# Stepping_Motor_DriverC.net
KiCad netlist of a schematic drawn in Altium Designer
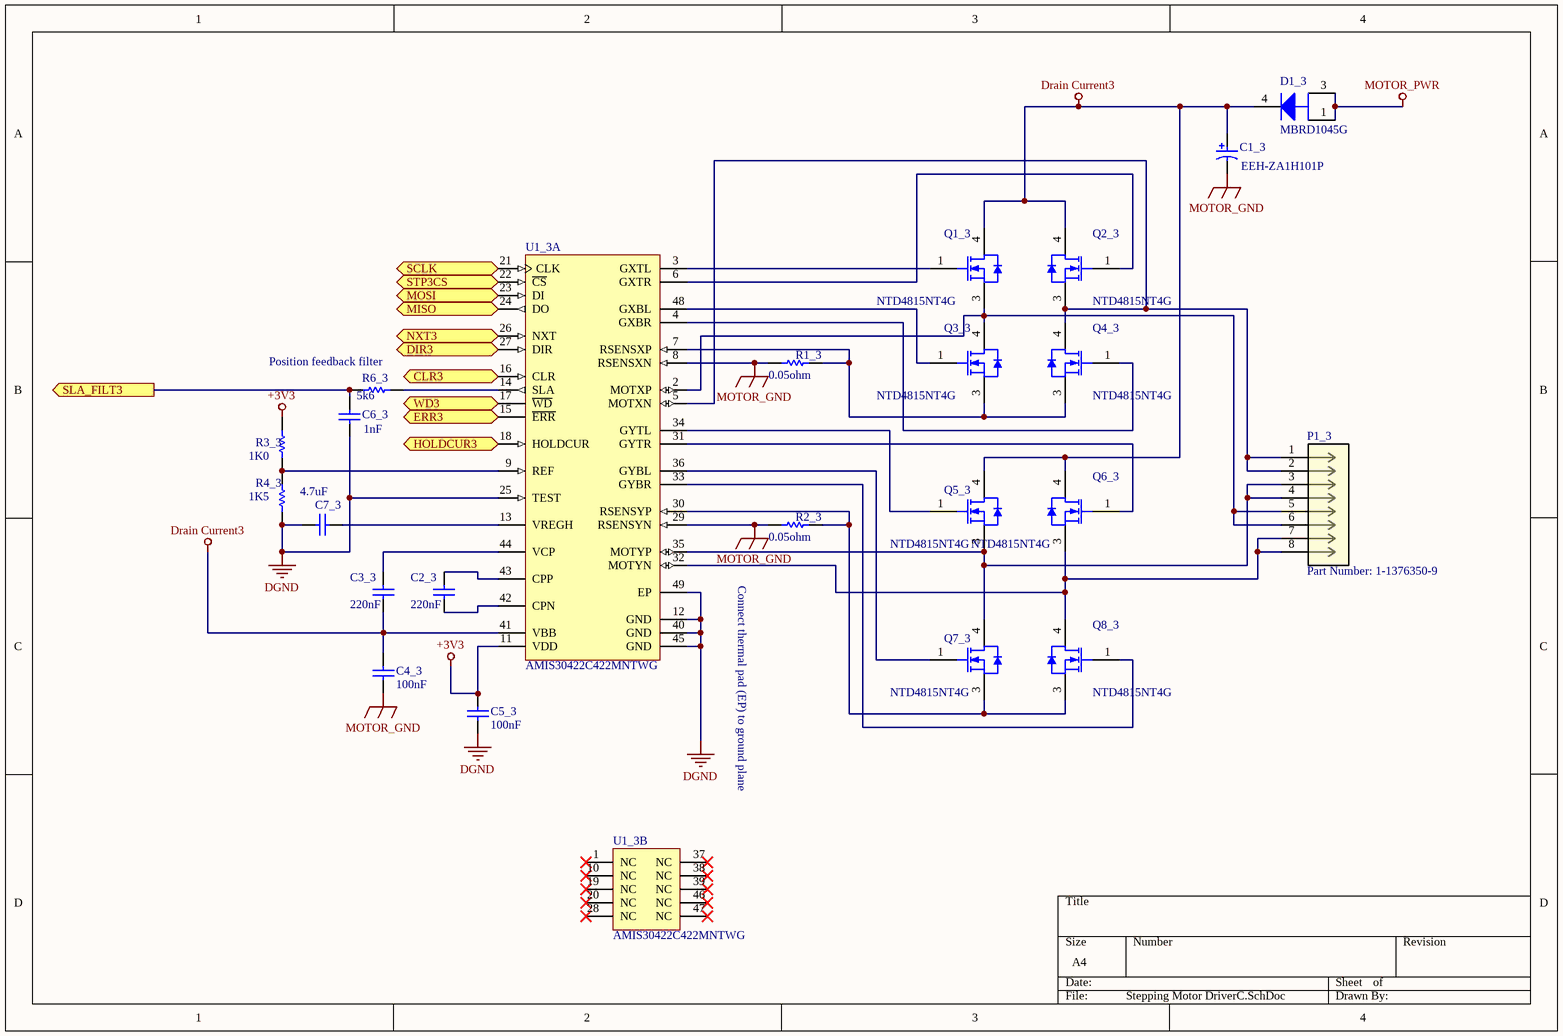
[diagram p0: Stepping Motor DriverC.SchDoc]

(export (version "E")
  (design (tool "Eeschema 10.0.6"))
  (components
    (comp (ref "C1_3")
      (value "EEH-ZA1H101P")
      (footprint "PNSC-ZA-G_L")
      (fields (field (name "TOLERANCE") "20%") (field (name "MANUFACTURER") "Panasonic"))
      (libsource (lib "Altium Content Vault") (part "CAP-P-2"))
    )
    (comp (ref "C2_3")
      (value "220nF")
      (footprint "CAPC0805(2012)75_L")
      (description "CAP 220nF 50V -20% to +80% 0805 (2012 Metric) Thickness 0.75mm SMD")
      (fields (field (name "TOLERANCE") "-20% to +80%") (field (name "Comment") "CAP 220nF 50V 0805(2012)"))
      (libsource (lib "Altium Content Vault") (part "CMP-1036-04556-1"))
    )
    (comp (ref "C3_3")
      (value "220nF")
      (footprint "CAPC0805(2012)75_L")
      (description "CAP 220nF 50V -20% to +80% 0805 (2012 Metric) Thickness 0.75mm SMD")
      (fields (field (name "TOLERANCE") "-20% to +80%") (field (name "Comment") "CAP 220nF 50V 0805(2012)"))
      (libsource (lib "Altium Content Vault") (part "CMP-1036-04556-1"))
    )
    (comp (ref "C4_3")
      (value "100nF")
      (footprint "CAPC1812(4532)110_N")
      (description "CAP 100nF 50V ±20% 1812 (4532 Metric) Thickness 1.1mm SMD")
      (fields (field (name "TOLERANCE") "Â±20%") (field (name "Comment") "CAP 100nF 50V 1812(4532)"))
      (libsource (lib "Altium Content Vault") (part "CMP-1040-01292-1"))
    )
    (comp (ref "C5_3")
      (value "100nF")
      (footprint "CAPC1812(4532)110_N")
      (description "CAP 100nF 50V ±20% 1812 (4532 Metric) Thickness 1.1mm SMD")
      (fields (field (name "TOLERANCE") "Â±20%") (field (name "Comment") "CAP 100nF 50V 1812(4532)"))
      (libsource (lib "Altium Content Vault") (part "CMP-1040-01292-1"))
    )
    (comp (ref "C6_3")
      (value "1nF")
      (footprint "CAPC1206(3216)170_N")
      (description "CAP 1nF 50V ±2% 1206 (3216 Metric) Thickness 1.7mm SMD")
      (fields (field (name "TOLERANCE") "Â±2%") (field (name "Comment") "CAP 1nF 50V 1206(3216)"))
      (libsource (lib "Altium Content Vault") (part "CMP-1037-02447-1"))
    )
    (comp (ref "C7_3")
      (value "4.7uF")
      (footprint "CAPC2220(5750)230_L")
      (description "CAP 4.7uF 50V ±10% 2220 (5750 Metric) Thickness 2.2mm SMD")
      (fields (field (name "TOLERANCE") "Â±10%") (field (name "Comment") "CAP 4.7uF 50V 2220(5750)"))
      (libsource (lib "Altium Content Vault") (part "CMP-1042-00755-1"))
    )
    (comp (ref "D1_3")
      (value "MBRD1045G")
      (footprint "ONSC-DPAK-3-369C-01_V")
      (description "SWITCHMODE(TM) Schottky Power Rectifier, 3-Pin DPAK, Pb-Free, Tube")
      (fields (field (name "MANUFACTURER") "On Semiconductor"))
      (libsource (lib "Altium Content Vault") (part "ONSC-D-A1A3K4-3_A"))
    )
    (comp (ref "P1_3")
      (value "Part Number: 1-1376350-9")
      (footprint "conn8_1-1376350-")
      (description "025 8POS CAP ASSY H TIN")
      (fields
        (field (name "MANUFACTURER_PART_NUMBER") "1-1376350-9")
        (field (name "COPYRIGHT") "Copyright (C) 2018 Accelerated Designs. All rights reserved")
      )
      (libsource (lib "2020-04-08_04-40-03") (part "1-1376350-9"))
    )
    (comp (ref "Q1_3")
      (value "NTD4815NT4G")
      (footprint "ONSC-DPAK-3-369AA-01_V")
      (description "Power MOSFET, 30 V, 35 A, Single N-Channel, 3-Pin DPAK, Pb-Free, Tape and Reel")
      (fields (field (name "MANUFACTURER") "On Semiconductor"))
      (libsource (lib "Altium Content Vault") (part "ONSC-NMOS-G1S3D4-3_B"))
    )
    (comp (ref "Q2_3")
      (value "NTD4815NT4G")
      (footprint "ONSC-DPAK-3-369AA-01_V")
      (description "Power MOSFET, 30 V, 35 A, Single N-Channel, 3-Pin DPAK, Pb-Free, Tape and Reel")
      (fields (field (name "MANUFACTURER") "On Semiconductor"))
      (libsource (lib "Altium Content Vault") (part "CMP-1058-00298-1"))
    )
    (comp (ref "Q3_3")
      (value "NTD4815NT4G")
      (footprint "ONSC-DPAK-3-369AA-01_V")
      (description "Power MOSFET, 30 V, 35 A, Single N-Channel, 3-Pin DPAK, Pb-Free, Tape and Reel")
      (fields (field (name "MANUFACTURER") "On Semiconductor"))
      (libsource (lib "Altium Content Vault") (part "ONSC-NMOS-G1S3D4-3_B"))
    )
    (comp (ref "Q4_3")
      (value "NTD4815NT4G")
      (footprint "ONSC-DPAK-3-369AA-01_V")
      (description "Power MOSFET, 30 V, 35 A, Single N-Channel, 3-Pin DPAK, Pb-Free, Tape and Reel")
      (fields (field (name "MANUFACTURER") "On Semiconductor"))
      (libsource (lib "Altium Content Vault") (part "CMP-1058-00298-1"))
    )
    (comp (ref "Q5_3")
      (value "NTD4815NT4G")
      (footprint "ONSC-DPAK-3-369AA-01_V")
      (description "Power MOSFET, 30 V, 35 A, Single N-Channel, 3-Pin DPAK, Pb-Free, Tape and Reel")
      (fields (field (name "MANUFACTURER") "On Semiconductor"))
      (libsource (lib "Altium Content Vault") (part "ONSC-NMOS-G1S3D4-3_B"))
    )
    (comp (ref "Q6_3")
      (value "NTD4815NT4G")
      (footprint "ONSC-DPAK-3-369AA-01_V")
      (description "Power MOSFET, 30 V, 35 A, Single N-Channel, 3-Pin DPAK, Pb-Free, Tape and Reel")
      (fields (field (name "MANUFACTURER") "On Semiconductor"))
      (libsource (lib "Altium Content Vault") (part "CMP-1058-00298-1"))
    )
    (comp (ref "Q7_3")
      (value "NTD4815NT4G")
      (footprint "ONSC-DPAK-3-369AA-01_V")
      (description "Power MOSFET, 30 V, 35 A, Single N-Channel, 3-Pin DPAK, Pb-Free, Tape and Reel")
      (fields (field (name "MANUFACTURER") "On Semiconductor"))
      (libsource (lib "Altium Content Vault") (part "ONSC-NMOS-G1S3D4-3_B"))
    )
    (comp (ref "Q8_3")
      (value "NTD4815NT4G")
      (footprint "ONSC-DPAK-3-369AA-01_V")
      (description "Power MOSFET, 30 V, 35 A, Single N-Channel, 3-Pin DPAK, Pb-Free, Tape and Reel")
      (fields (field (name "MANUFACTURER") "On Semiconductor"))
      (libsource (lib "Altium Content Vault") (part "CMP-1058-00298-1"))
    )
    (comp (ref "R1_3")
      (value "WSL2512R0500FEA")
      (footprint "RESC6432X89X76LL25T25")
      (description "Chip Resistor, 50 mOhm, +/- 1%, 1 W, -65 to 170 degC, 2512 (6432 Metric), RoHS, Tape and Reel")
      (fields (field (name "MANUFACTURER") "Vishay") (field (name "RESISTANCE") "0.05ohm"))
      (libsource (lib "Altium Content Vault") (part "CMP-2000-07420-1"))
    )
    (comp (ref "R2_3")
      (value "WSL2512R0500FEA")
      (footprint "RESC6432X89X76LL25T25")
      (description "Chip Resistor, 50 mOhm, +/- 1%, 1 W, -65 to 170 degC, 2512 (6432 Metric), RoHS, Tape and Reel")
      (fields (field (name "MANUFACTURER") "Vishay") (field (name "RESISTANCE") "0.05ohm"))
      (libsource (lib "Altium Content Vault") (part "CMP-2000-07420-1"))
    )
    (comp (ref "R3_3")
      (value "1K0")
      (footprint "RESC0805(2012)_M")
      (description "1K 0.125W 1% 0805 (2012 Metric)  SMD")
      (fields (field (name "TOLERANCE") "1 %") (field (name "POWER") "0.125 W"))
      (libsource (lib "Altium Content Vault") (part "CMP-1013-00510-1"))
    )
    (comp (ref "R4_3")
      (value "1K5")
      (footprint "RESC0805(2012)_M")
      (description "1K5 0.125W 1% 0805 (2012 Metric)  SMD")
      (fields (field (name "POWER") "0.125 W") (field (name "TOLERANCE") "1 %"))
      (libsource (lib "Altium Content Vault") (part "CMP-1013-00528-1"))
    )
    (comp (ref "R6_3")
      (value "5k6")
      (footprint "RESC0805(2012)_L")
      (description "5K6 0.125W 1% 0805 (2012 Metric)  SMD")
      (fields (field (name "POWER") "0.125 W") (field (name "TOLERANCE") "1 %"))
      (libsource (lib "Altium Content Vault") (part "CMP-1013-00595-1"))
    )
    (comp (ref "U1_3")
      (value "AMIS30422C422MNTWG")
      (footprint "ONSC-QFN-48-485AJ-01_V")
      (fields (field (name "MANUFACTURER") "ON Semiconductor"))
      (libsource (lib "Altium Content Vault") (part "ONSC-AMIS-30422-QFN-48"))
    )
  )
  (nets
    (net (code "1") (name "+3V3") (class "Default")
      (node (ref "C5_3") (pin "2") (pinfunction "2_2") (pintype "passive"))
      (node (ref "R3_3") (pin "2") (pinfunction "2_2") (pintype "passive"))
      (node (ref "U1_3") (pin "11") (pinfunction "VDD_11") (pintype "power_in"))
    )
    (net (code "2") (name "/CLR3") (class "Default")
      (node (ref "U1_3") (pin "16") (pinfunction "CLR_16") (pintype "input"))
    )
    (net (code "3") (name "/DIR3") (class "Default")
      (node (ref "U1_3") (pin "27") (pinfunction "DIR_27") (pintype "input"))
    )
    (net (code "4") (name "/ERR3") (class "Default")
      (node (ref "U1_3") (pin "15") (pinfunction "~{ERR}_15") (pintype "tri_state"))
    )
    (net (code "5") (name "/HOLDCUR3") (class "Default")
      (node (ref "U1_3") (pin "18") (pinfunction "HOLDCUR_18") (pintype "input"))
    )
    (net (code "6") (name "/MISO") (class "Default")
      (node (ref "U1_3") (pin "24") (pinfunction "DO_24") (pintype "output"))
    )
    (net (code "7") (name "/MOSI") (class "Default")
      (node (ref "U1_3") (pin "23") (pinfunction "DI_23") (pintype "input"))
    )
    (net (code "8") (name "/NXT3") (class "Default")
      (node (ref "U1_3") (pin "26") (pinfunction "NXT_26") (pintype "input"))
    )
    (net (code "9") (name "/SCLK") (class "Default")
      (node (ref "U1_3") (pin "21") (pinfunction "CLK_21") (pintype "input"))
    )
    (net (code "10") (name "/SLA_FILT3") (class "Default")
      (node (ref "C6_3") (pin "2") (pinfunction "2_2") (pintype "passive"))
      (node (ref "R6_3") (pin "1") (pinfunction "1_1") (pintype "passive"))
    )
    (net (code "11") (name "/STP3CS") (class "Default")
      (node (ref "U1_3") (pin "22") (pinfunction "~{CS}_22") (pintype "input"))
    )
    (net (code "12") (name "/WD3") (class "Default")
      (node (ref "U1_3") (pin "17") (pinfunction "~{WD}_17") (pintype "tri_state"))
    )
    (net (code "13") (name "DGND") (class "Default")
      (node (ref "C5_3") (pin "1") (pinfunction "1_1") (pintype "passive"))
      (node (ref "C6_3") (pin "1") (pinfunction "1_1") (pintype "passive"))
      (node (ref "C7_3") (pin "1") (pinfunction "1_1") (pintype "passive"))
      (node (ref "R4_3") (pin "1") (pinfunction "1_1") (pintype "passive"))
      (node (ref "U1_3") (pin "12") (pinfunction "GND_12") (pintype "power_in"))
      (node (ref "U1_3") (pin "25") (pinfunction "TEST_25") (pintype "input"))
      (node (ref "U1_3") (pin "40") (pinfunction "GND_40") (pintype "power_in"))
      (node (ref "U1_3") (pin "45") (pinfunction "GND_45") (pintype "power_in"))
      (node (ref "U1_3") (pin "49") (pinfunction "EP_49") (pintype "passive"))
    )
    (net (code "14") (name "Drain Current3") (class "Default")
      (node (ref "C1_3") (pin "1") (pinfunction "1_1") (pintype "passive"))
      (node (ref "C3_3") (pin "1") (pinfunction "1_1") (pintype "passive"))
      (node (ref "C4_3") (pin "2") (pinfunction "2_2") (pintype "passive"))
      (node (ref "D1_3") (pin "4") (pinfunction "K_4") (pintype "passive"))
      (node (ref "Q1_3") (pin "4") (pinfunction "D_4") (pintype "passive"))
      (node (ref "Q2_3") (pin "4") (pinfunction "D_4") (pintype "passive"))
      (node (ref "Q5_3") (pin "4") (pinfunction "D_4") (pintype "passive"))
      (node (ref "Q6_3") (pin "4") (pinfunction "D_4") (pintype "passive"))
      (node (ref "U1_3") (pin "41") (pinfunction "VBB_41") (pintype "power_in"))
    )
    (net (code "15") (name "MOTOR_GND") (class "Default")
      (node (ref "C1_3") (pin "2") (pinfunction "2_2") (pintype "passive"))
      (node (ref "C4_3") (pin "1") (pinfunction "1_1") (pintype "passive"))
      (node (ref "R1_3") (pin "1") (pinfunction "1_1") (pintype "passive"))
      (node (ref "R2_3") (pin "1") (pinfunction "1_1") (pintype "passive"))
      (node (ref "U1_3") (pin "29") (pinfunction "RSENSYN_29") (pintype "input"))
      (node (ref "U1_3") (pin "8") (pinfunction "RSENSXN_8") (pintype "input"))
    )
    (net (code "16") (name "MOTOR_PWR") (class "Default")
      (node (ref "D1_3") (pin "1") (pinfunction "A_1") (pintype "passive"))
      (node (ref "D1_3") (pin "3") (pinfunction "A_3") (pintype "passive"))
    )
    (net (code "17") (name "Net-(Q1_3-G)") (class "Default")
      (node (ref "Q1_3") (pin "1") (pinfunction "G_1") (pintype "passive"))
      (node (ref "U1_3") (pin "3") (pinfunction "GXTL_3") (pintype "tri_state"))
    )
    (net (code "18") (name "Net-(Q1_3-S)") (class "Default")
      (node (ref "P1_3") (pin "5") (pinfunction "5_5") (pintype "passive"))
      (node (ref "P1_3") (pin "6") (pinfunction "6_6") (pintype "passive"))
      (node (ref "Q1_3") (pin "3") (pinfunction "S_3") (pintype "passive"))
      (node (ref "Q3_3") (pin "4") (pinfunction "D_4") (pintype "passive"))
      (node (ref "U1_3") (pin "2") (pinfunction "MOTXP_2") (pintype "bidirectional"))
    )
    (net (code "19") (name "Net-(Q2_3-G)") (class "Default")
      (node (ref "Q2_3") (pin "1") (pinfunction "G_1") (pintype "passive"))
      (node (ref "U1_3") (pin "6") (pinfunction "GXTR_6") (pintype "tri_state"))
    )
    (net (code "20") (name "Net-(Q2_3-S)") (class "Default")
      (node (ref "P1_3") (pin "1") (pinfunction "1_1") (pintype "passive"))
      (node (ref "P1_3") (pin "2") (pinfunction "2_2") (pintype "passive"))
      (node (ref "Q2_3") (pin "3") (pinfunction "S_3") (pintype "passive"))
      (node (ref "Q4_3") (pin "4") (pinfunction "D_4") (pintype "passive"))
      (node (ref "U1_3") (pin "5") (pinfunction "MOTXN_5") (pintype "bidirectional"))
    )
    (net (code "21") (name "Net-(Q3_3-G)") (class "Default")
      (node (ref "Q3_3") (pin "1") (pinfunction "G_1") (pintype "passive"))
      (node (ref "U1_3") (pin "48") (pinfunction "GXBL_48") (pintype "tri_state"))
    )
    (net (code "22") (name "Net-(Q3_3-S)") (class "Default")
      (node (ref "Q3_3") (pin "3") (pinfunction "S_3") (pintype "passive"))
      (node (ref "Q4_3") (pin "3") (pinfunction "S_3") (pintype "passive"))
      (node (ref "R1_3") (pin "2") (pinfunction "2_2") (pintype "passive"))
      (node (ref "U1_3") (pin "7") (pinfunction "RSENSXP_7") (pintype "input"))
    )
    (net (code "23") (name "Net-(Q4_3-G)") (class "Default")
      (node (ref "Q4_3") (pin "1") (pinfunction "G_1") (pintype "passive"))
      (node (ref "U1_3") (pin "4") (pinfunction "GXBR_4") (pintype "tri_state"))
    )
    (net (code "24") (name "Net-(Q5_3-G)") (class "Default")
      (node (ref "Q5_3") (pin "1") (pinfunction "G_1") (pintype "passive"))
      (node (ref "U1_3") (pin "34") (pinfunction "GYTL_34") (pintype "tri_state"))
    )
    (net (code "25") (name "Net-(Q5_3-S)") (class "Default")
      (node (ref "P1_3") (pin "3") (pinfunction "3_3") (pintype "passive"))
      (node (ref "P1_3") (pin "4") (pinfunction "4_4") (pintype "passive"))
      (node (ref "Q5_3") (pin "3") (pinfunction "S_3") (pintype "passive"))
      (node (ref "Q7_3") (pin "4") (pinfunction "D_4") (pintype "passive"))
      (node (ref "U1_3") (pin "35") (pinfunction "MOTYP_35") (pintype "bidirectional"))
    )
    (net (code "26") (name "Net-(Q6_3-G)") (class "Default")
      (node (ref "Q6_3") (pin "1") (pinfunction "G_1") (pintype "passive"))
      (node (ref "U1_3") (pin "31") (pinfunction "GYTR_31") (pintype "tri_state"))
    )
    (net (code "27") (name "Net-(Q6_3-S)") (class "Default")
      (node (ref "P1_3") (pin "7") (pinfunction "7_7") (pintype "passive"))
      (node (ref "P1_3") (pin "8") (pinfunction "8_8") (pintype "passive"))
      (node (ref "Q6_3") (pin "3") (pinfunction "S_3") (pintype "passive"))
      (node (ref "Q8_3") (pin "4") (pinfunction "D_4") (pintype "passive"))
      (node (ref "U1_3") (pin "32") (pinfunction "MOTYN_32") (pintype "bidirectional"))
    )
    (net (code "28") (name "Net-(Q7_3-G)") (class "Default")
      (node (ref "Q7_3") (pin "1") (pinfunction "G_1") (pintype "passive"))
      (node (ref "U1_3") (pin "36") (pinfunction "GYBL_36") (pintype "tri_state"))
    )
    (net (code "29") (name "Net-(Q7_3-S)") (class "Default")
      (node (ref "Q7_3") (pin "3") (pinfunction "S_3") (pintype "passive"))
      (node (ref "Q8_3") (pin "3") (pinfunction "S_3") (pintype "passive"))
      (node (ref "R2_3") (pin "2") (pinfunction "2_2") (pintype "passive"))
      (node (ref "U1_3") (pin "30") (pinfunction "RSENSYP_30") (pintype "input"))
    )
    (net (code "30") (name "Net-(Q8_3-G)") (class "Default")
      (node (ref "Q8_3") (pin "1") (pinfunction "G_1") (pintype "passive"))
      (node (ref "U1_3") (pin "33") (pinfunction "GYBR_33") (pintype "tri_state"))
    )
    (net (code "31") (name "Net-(U1_3A-CPN)") (class "Default")
      (node (ref "C2_3") (pin "1") (pinfunction "1_1") (pintype "passive"))
      (node (ref "U1_3") (pin "42") (pinfunction "CPN_42") (pintype "passive"))
    )
    (net (code "32") (name "Net-(U1_3A-CPP)") (class "Default")
      (node (ref "C2_3") (pin "2") (pinfunction "2_2") (pintype "passive"))
      (node (ref "U1_3") (pin "43") (pinfunction "CPP_43") (pintype "passive"))
    )
    (net (code "33") (name "Net-(U1_3A-REF)") (class "Default")
      (node (ref "R3_3") (pin "1") (pinfunction "1_1") (pintype "passive"))
      (node (ref "R4_3") (pin "2") (pinfunction "2_2") (pintype "passive"))
      (node (ref "U1_3") (pin "9") (pinfunction "REF_9") (pintype "input"))
    )
    (net (code "34") (name "Net-(U1_3A-SLA)") (class "Default")
      (node (ref "R6_3") (pin "2") (pinfunction "2_2") (pintype "passive"))
      (node (ref "U1_3") (pin "14") (pinfunction "SLA_14") (pintype "output"))
    )
    (net (code "35") (name "Net-(U1_3A-VCP)") (class "Default")
      (node (ref "C3_3") (pin "2") (pinfunction "2_2") (pintype "passive"))
      (node (ref "U1_3") (pin "44") (pinfunction "VCP_44") (pintype "passive"))
    )
    (net (code "36") (name "Net-(U1_3A-VREGH)") (class "Default")
      (node (ref "C7_3") (pin "2") (pinfunction "2_2") (pintype "passive"))
      (node (ref "U1_3") (pin "13") (pinfunction "VREGH_13") (pintype "power_in"))
    )
    (net (code "37") (name "unconnected-(U1_3B-NC-Pad1)") (class "Default")
      (node (ref "U1_3") (pin "1") (pinfunction "NC_1") (pintype "passive+no_connect"))
    )
    (net (code "38") (name "unconnected-(U1_3B-NC-Pad10)") (class "Default")
      (node (ref "U1_3") (pin "10") (pinfunction "NC_10") (pintype "passive+no_connect"))
    )
    (net (code "39") (name "unconnected-(U1_3B-NC-Pad19)") (class "Default")
      (node (ref "U1_3") (pin "19") (pinfunction "NC_19") (pintype "passive+no_connect"))
    )
    (net (code "40") (name "unconnected-(U1_3B-NC-Pad20)") (class "Default")
      (node (ref "U1_3") (pin "20") (pinfunction "NC_20") (pintype "passive+no_connect"))
    )
    (net (code "41") (name "unconnected-(U1_3B-NC-Pad28)") (class "Default")
      (node (ref "U1_3") (pin "28") (pinfunction "NC_28") (pintype "passive+no_connect"))
    )
    (net (code "42") (name "unconnected-(U1_3B-NC-Pad37)") (class "Default")
      (node (ref "U1_3") (pin "37") (pinfunction "NC_37") (pintype "passive+no_connect"))
    )
    (net (code "43") (name "unconnected-(U1_3B-NC-Pad38)") (class "Default")
      (node (ref "U1_3") (pin "38") (pinfunction "NC_38") (pintype "passive+no_connect"))
    )
    (net (code "44") (name "unconnected-(U1_3B-NC-Pad39)") (class "Default")
      (node (ref "U1_3") (pin "39") (pinfunction "NC_39") (pintype "passive+no_connect"))
    )
    (net (code "45") (name "unconnected-(U1_3B-NC-Pad46)") (class "Default")
      (node (ref "U1_3") (pin "46") (pinfunction "NC_46") (pintype "passive+no_connect"))
    )
    (net (code "46") (name "unconnected-(U1_3B-NC-Pad47)") (class "Default")
      (node (ref "U1_3") (pin "47") (pinfunction "NC_47") (pintype "passive+no_connect"))
    )
  )
)
